# Fan_Control.net
KiCad netlist of a schematic drawn in Altium Designer
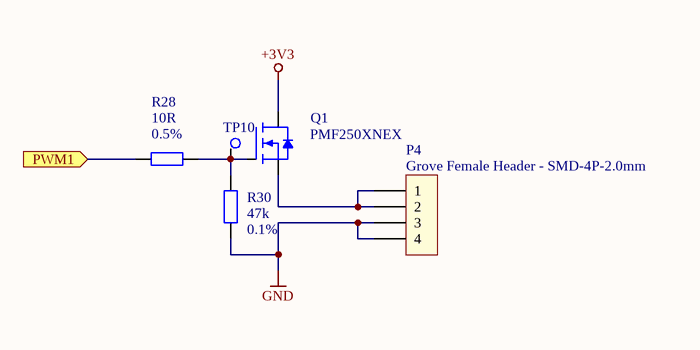
[diagram p0: Fan_Control.SchDoc]

(export (version "E")
  (design (tool "Eeschema 10.0.6"))
  (components
    (comp (ref "P4")
      (value "P_Header_4")
      (footprint "CONN_114020164")
      (description "Grove Female Header - SMD-4P-2.0mm")
      (fields
        (field (name "DESC") "Grove Female Header - SMD-4P-2.0mm")
        (field (name "PART NUMBER") "114020164")
        (field (name "MANUFACTURER") "SEEED")
      )
      (libsource (lib "ProgresjaSpace") (part "P_Header_4"))
    )
    (comp (ref "Q1")
      (value "PMF250XNEX")
      (footprint "SOT323")
      (description "30V 1A Single N-Channel")
      (fields (field (name "MANUFACTURER") "NEXPERIA") (field (name "Comment") "Q_NMOSFET"))
      (libsource (lib "ProgresjaSpace") (part "Q_NMOSFET"))
    )
    (comp (ref "R28")
      (value "10R")
      (footprint "R_0603")
      (fields
        (field (name "TOLERANCE") "0.5%")
        (field (name "PART NUMBER") "R_10R_75V_0603")
        (field (name "VOLTAGE") "75V")
        (field (name "MANUFACTURER") "Vishay")
      )
      (libsource (lib "ProgresjaSpace") (part "R"))
    )
    (comp (ref "R30")
      (value "47k")
      (footprint "R_0402")
      (fields
        (field (name "TOLERANCE") "0.1%")
        (field (name "PART NUMBER") "R_47k_50V_0402")
        (field (name "VOLTAGE") "50V")
        (field (name "MANUFACTURER") "Vishay")
      )
      (libsource (lib "") (part "R_1"))
    )
    (comp (ref "TP10")
      (value "TP_TestPoint")
      (footprint "TP_01")
      (fields (field (name "PART NUMBER") "TestPoint1") (field (name "MANUFACTURER") "Progresja Space"))
      (libsource (lib "ProgresjaSpace") (part "TP_TestPoint"))
    )
  )
  (nets
    (net (code "1") (name "+3V3") (class "Default")
      (node (ref "Q1") (pin "3") (pinfunction "D_3") (pintype "passive"))
    )
    (net (code "2") (name "/PWM1") (class "Default")
      (node (ref "R28") (pin "1") (pinfunction "1_1") (pintype "passive"))
    )
    (net (code "3") (name "GND") (class "Default")
      (node (ref "P4") (pin "3") (pinfunction "3_3") (pintype "passive"))
      (node (ref "P4") (pin "4") (pinfunction "4_4") (pintype "passive"))
      (node (ref "R30") (pin "2") (pinfunction "2_2") (pintype "passive"))
    )
    (net (code "4") (name "Net-(Q1-G)") (class "Default")
      (node (ref "Q1") (pin "1") (pinfunction "G_1") (pintype "passive"))
      (node (ref "R28") (pin "2") (pinfunction "2_2") (pintype "passive"))
      (node (ref "R30") (pin "1") (pinfunction "1_1") (pintype "passive"))
      (node (ref "TP10") (pin "1") (pinfunction "1_1") (pintype "passive"))
    )
    (net (code "5") (name "Net-(Q1-S)") (class "Default")
      (node (ref "P4") (pin "1") (pinfunction "1_1") (pintype "passive"))
      (node (ref "P4") (pin "2") (pinfunction "2_2") (pintype "passive"))
      (node (ref "Q1") (pin "2") (pinfunction "S_2") (pintype "passive"))
    )
  )
)
